# BUS_OUT.net
KiCad netlist of a schematic drawn in EAGLE
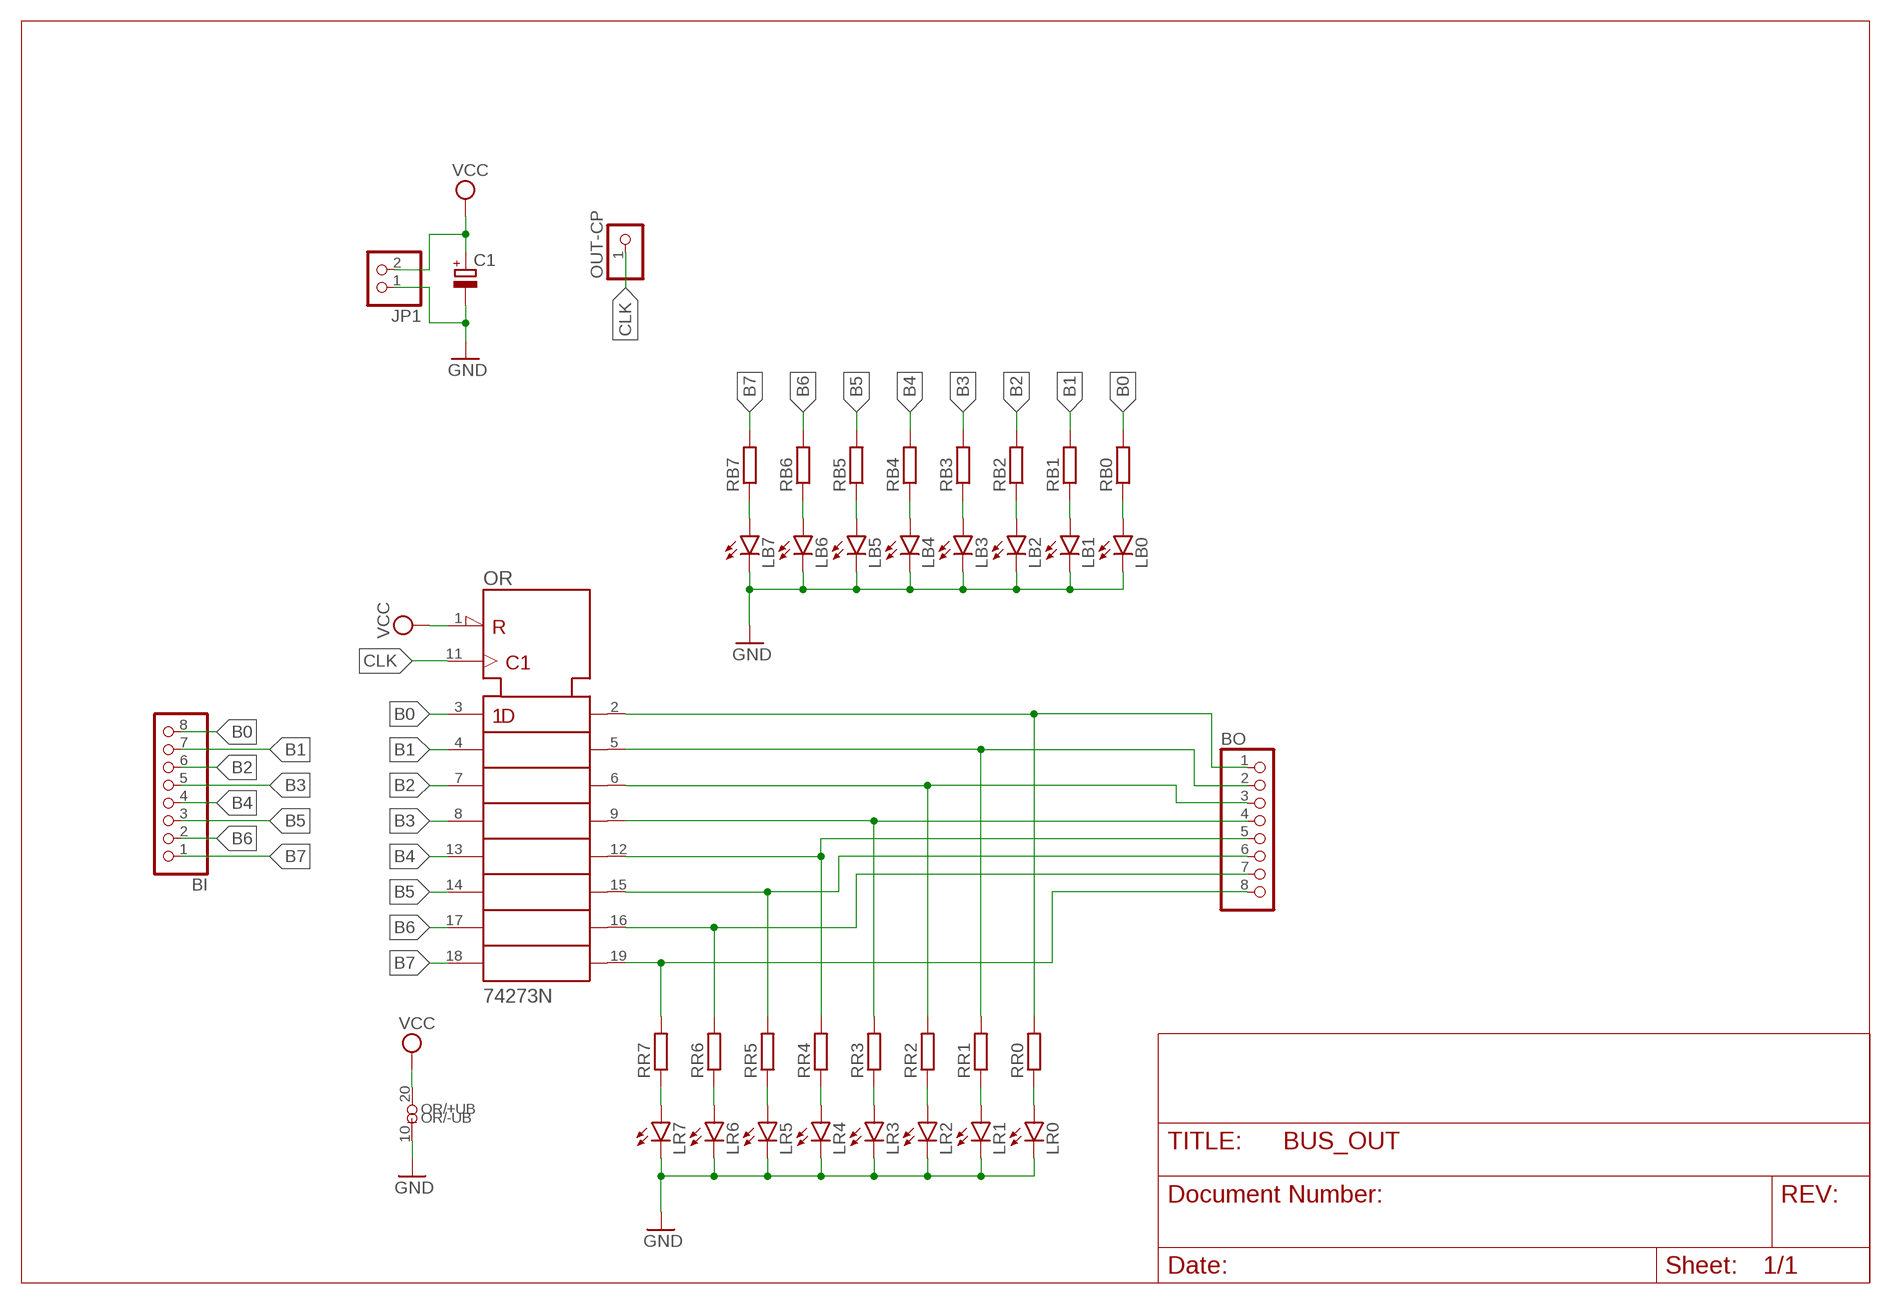
[diagram p0: schematic, sheet 1]

(export (version "E")
  (design (tool "Eeschema 10.0.6"))
  (components
    (comp (ref "BI")
      (value "PINHD-1X8")
      (footprint "eagle-import:1X08")
      (libsource (lib "eagle-import") (part "PINHD-1X8"))
    )
    (comp (ref "BO")
      (value "PINHD-1X8")
      (footprint "eagle-import:1X08")
      (libsource (lib "eagle-import") (part "PINHD-1X8"))
    )
    (comp (ref "C1")
      (value "CPOL-EUE2.5-6")
      (footprint "eagle-import:E2,5-6")
      (libsource (lib "eagle-import") (part "CPOL-EUE2.5-6"))
    )
    (comp (ref "JP1")
      (value "PINHD-1X2")
      (footprint "eagle-import:1X02")
      (libsource (lib "eagle-import") (part "PINHD-1X2"))
    )
    (comp (ref "LB0")
      (value "LED5MM")
      (footprint "eagle-import:LED5MM")
      (libsource (lib "eagle-import") (part "LED5MM"))
    )
    (comp (ref "LB1")
      (value "LED5MM")
      (footprint "eagle-import:LED5MM")
      (libsource (lib "eagle-import") (part "LED5MM"))
    )
    (comp (ref "LB2")
      (value "LED5MM")
      (footprint "eagle-import:LED5MM")
      (libsource (lib "eagle-import") (part "LED5MM"))
    )
    (comp (ref "LB3")
      (value "LED5MM")
      (footprint "eagle-import:LED5MM")
      (libsource (lib "eagle-import") (part "LED5MM"))
    )
    (comp (ref "LB4")
      (value "LED5MM")
      (footprint "eagle-import:LED5MM")
      (libsource (lib "eagle-import") (part "LED5MM"))
    )
    (comp (ref "LB5")
      (value "LED5MM")
      (footprint "eagle-import:LED5MM")
      (libsource (lib "eagle-import") (part "LED5MM"))
    )
    (comp (ref "LB6")
      (value "LED5MM")
      (footprint "eagle-import:LED5MM")
      (libsource (lib "eagle-import") (part "LED5MM"))
    )
    (comp (ref "LB7")
      (value "LED5MM")
      (footprint "eagle-import:LED5MM")
      (libsource (lib "eagle-import") (part "LED5MM"))
    )
    (comp (ref "LR0")
      (value "LED5MM")
      (footprint "eagle-import:LED5MM")
      (libsource (lib "eagle-import") (part "LED5MM"))
    )
    (comp (ref "LR1")
      (value "LED5MM")
      (footprint "eagle-import:LED5MM")
      (libsource (lib "eagle-import") (part "LED5MM"))
    )
    (comp (ref "LR2")
      (value "LED5MM")
      (footprint "eagle-import:LED5MM")
      (libsource (lib "eagle-import") (part "LED5MM"))
    )
    (comp (ref "LR3")
      (value "LED5MM")
      (footprint "eagle-import:LED5MM")
      (libsource (lib "eagle-import") (part "LED5MM"))
    )
    (comp (ref "LR4")
      (value "LED5MM")
      (footprint "eagle-import:LED5MM")
      (libsource (lib "eagle-import") (part "LED5MM"))
    )
    (comp (ref "LR5")
      (value "LED5MM")
      (footprint "eagle-import:LED5MM")
      (libsource (lib "eagle-import") (part "LED5MM"))
    )
    (comp (ref "LR6")
      (value "LED5MM")
      (footprint "eagle-import:LED5MM")
      (libsource (lib "eagle-import") (part "LED5MM"))
    )
    (comp (ref "LR7")
      (value "LED5MM")
      (footprint "eagle-import:LED5MM")
      (libsource (lib "eagle-import") (part "LED5MM"))
    )
    (comp (ref "OR")
      (value "74273N")
      (footprint "eagle-import:DIL20")
      (libsource (lib "eagle-import") (part "74273N"))
    )
    (comp (ref "OUT-CP")
      (value "PINHD-1X1")
      (footprint "eagle-import:1X01")
      (libsource (lib "eagle-import") (part "PINHD-1X1"))
    )
    (comp (ref "RB0")
      (value "R-EU_0204/7")
      (footprint "eagle-import:0204_7")
      (libsource (lib "eagle-import") (part "R-EU_0204/7"))
    )
    (comp (ref "RB1")
      (value "R-EU_0204/7")
      (footprint "eagle-import:0204_7")
      (libsource (lib "eagle-import") (part "R-EU_0204/7"))
    )
    (comp (ref "RB2")
      (value "R-EU_0204/7")
      (footprint "eagle-import:0204_7")
      (libsource (lib "eagle-import") (part "R-EU_0204/7"))
    )
    (comp (ref "RB3")
      (value "R-EU_0204/7")
      (footprint "eagle-import:0204_7")
      (libsource (lib "eagle-import") (part "R-EU_0204/7"))
    )
    (comp (ref "RB4")
      (value "R-EU_0204/7")
      (footprint "eagle-import:0204_7")
      (libsource (lib "eagle-import") (part "R-EU_0204/7"))
    )
    (comp (ref "RB5")
      (value "R-EU_0204/7")
      (footprint "eagle-import:0204_7")
      (libsource (lib "eagle-import") (part "R-EU_0204/7"))
    )
    (comp (ref "RB6")
      (value "R-EU_0204/7")
      (footprint "eagle-import:0204_7")
      (libsource (lib "eagle-import") (part "R-EU_0204/7"))
    )
    (comp (ref "RB7")
      (value "R-EU_0204/7")
      (footprint "eagle-import:0204_7")
      (libsource (lib "eagle-import") (part "R-EU_0204/7"))
    )
    (comp (ref "RR0")
      (value "R-EU_0204/7")
      (footprint "eagle-import:0204_7")
      (libsource (lib "eagle-import") (part "R-EU_0204/7"))
    )
    (comp (ref "RR1")
      (value "R-EU_0204/7")
      (footprint "eagle-import:0204_7")
      (libsource (lib "eagle-import") (part "R-EU_0204/7"))
    )
    (comp (ref "RR2")
      (value "R-EU_0204/7")
      (footprint "eagle-import:0204_7")
      (libsource (lib "eagle-import") (part "R-EU_0204/7"))
    )
    (comp (ref "RR3")
      (value "R-EU_0204/7")
      (footprint "eagle-import:0204_7")
      (libsource (lib "eagle-import") (part "R-EU_0204/7"))
    )
    (comp (ref "RR4")
      (value "R-EU_0204/7")
      (footprint "eagle-import:0204_7")
      (libsource (lib "eagle-import") (part "R-EU_0204/7"))
    )
    (comp (ref "RR5")
      (value "R-EU_0204/7")
      (footprint "eagle-import:0204_7")
      (libsource (lib "eagle-import") (part "R-EU_0204/7"))
    )
    (comp (ref "RR6")
      (value "R-EU_0204/7")
      (footprint "eagle-import:0204_7")
      (libsource (lib "eagle-import") (part "R-EU_0204/7"))
    )
    (comp (ref "RR7")
      (value "R-EU_0204/7")
      (footprint "eagle-import:0204_7")
      (libsource (lib "eagle-import") (part "R-EU_0204/7"))
    )
  )
  (nets
    (net (code "1") (name "B0") (class "Default")
      (node (ref "BI") (pin "8") (pinfunction "8_8") (pintype "passive"))
      (node (ref "OR") (pin "3") (pinfunction "1D_3") (pintype "input"))
      (node (ref "RB0") (pin "2") (pinfunction "2_2") (pintype "passive"))
    )
    (net (code "2") (name "B1") (class "Default")
      (node (ref "BI") (pin "7") (pinfunction "7_7") (pintype "passive"))
      (node (ref "OR") (pin "4") (pinfunction "2D_4") (pintype "input"))
      (node (ref "RB1") (pin "2") (pinfunction "2_2") (pintype "passive"))
    )
    (net (code "3") (name "B2") (class "Default")
      (node (ref "BI") (pin "6") (pinfunction "6_6") (pintype "passive"))
      (node (ref "OR") (pin "7") (pinfunction "3D_7") (pintype "input"))
      (node (ref "RB2") (pin "2") (pinfunction "2_2") (pintype "passive"))
    )
    (net (code "4") (name "B3") (class "Default")
      (node (ref "BI") (pin "5") (pinfunction "5_5") (pintype "passive"))
      (node (ref "OR") (pin "8") (pinfunction "4D_8") (pintype "input"))
      (node (ref "RB3") (pin "2") (pinfunction "2_2") (pintype "passive"))
    )
    (net (code "5") (name "B4") (class "Default")
      (node (ref "BI") (pin "4") (pinfunction "4_4") (pintype "passive"))
      (node (ref "OR") (pin "13") (pinfunction "5D_13") (pintype "input"))
      (node (ref "RB4") (pin "2") (pinfunction "2_2") (pintype "passive"))
    )
    (net (code "6") (name "B5") (class "Default")
      (node (ref "BI") (pin "3") (pinfunction "3_3") (pintype "passive"))
      (node (ref "OR") (pin "14") (pinfunction "6D_14") (pintype "input"))
      (node (ref "RB5") (pin "2") (pinfunction "2_2") (pintype "passive"))
    )
    (net (code "7") (name "B6") (class "Default")
      (node (ref "BI") (pin "2") (pinfunction "2_2") (pintype "passive"))
      (node (ref "OR") (pin "17") (pinfunction "7D_17") (pintype "input"))
      (node (ref "RB6") (pin "2") (pinfunction "2_2") (pintype "passive"))
    )
    (net (code "8") (name "B7") (class "Default")
      (node (ref "BI") (pin "1") (pinfunction "1_1") (pintype "passive"))
      (node (ref "OR") (pin "18") (pinfunction "8D_18") (pintype "input"))
      (node (ref "RB7") (pin "2") (pinfunction "2_2") (pintype "passive"))
    )
    (net (code "9") (name "CLK") (class "Default")
      (node (ref "OR") (pin "11") (pinfunction "CLK_11") (pintype "input"))
      (node (ref "OUT-CP") (pin "1") (pinfunction "1_1") (pintype "passive"))
    )
    (net (code "10") (name "GND") (class "Default")
      (node (ref "C1") (pin "-") (pinfunction "-_-") (pintype "passive"))
      (node (ref "JP1") (pin "1") (pinfunction "1_1") (pintype "passive"))
      (node (ref "LB0") (pin "K") (pinfunction "C_K") (pintype "passive"))
      (node (ref "LB1") (pin "K") (pinfunction "C_K") (pintype "passive"))
      (node (ref "LB2") (pin "K") (pinfunction "C_K") (pintype "passive"))
      (node (ref "LB3") (pin "K") (pinfunction "C_K") (pintype "passive"))
      (node (ref "LB4") (pin "K") (pinfunction "C_K") (pintype "passive"))
      (node (ref "LB5") (pin "K") (pinfunction "C_K") (pintype "passive"))
      (node (ref "LB6") (pin "K") (pinfunction "C_K") (pintype "passive"))
      (node (ref "LB7") (pin "K") (pinfunction "C_K") (pintype "passive"))
      (node (ref "LR0") (pin "K") (pinfunction "C_K") (pintype "passive"))
      (node (ref "LR1") (pin "K") (pinfunction "C_K") (pintype "passive"))
      (node (ref "LR2") (pin "K") (pinfunction "C_K") (pintype "passive"))
      (node (ref "LR3") (pin "K") (pinfunction "C_K") (pintype "passive"))
      (node (ref "LR4") (pin "K") (pinfunction "C_K") (pintype "passive"))
      (node (ref "LR5") (pin "K") (pinfunction "C_K") (pintype "passive"))
      (node (ref "LR6") (pin "K") (pinfunction "C_K") (pintype "passive"))
      (node (ref "LR7") (pin "K") (pinfunction "C_K") (pintype "passive"))
      (node (ref "OR") (pin "10") (pinfunction "-UB_10") (pintype "power_in"))
    )
    (net (code "11") (name "Net-(LB0-PadA)") (class "Default")
      (node (ref "LB0") (pin "A") (pinfunction "A_A") (pintype "passive"))
      (node (ref "RB0") (pin "1") (pinfunction "1_1") (pintype "passive"))
    )
    (net (code "12") (name "Net-(LB1-PadA)") (class "Default")
      (node (ref "LB1") (pin "A") (pinfunction "A_A") (pintype "passive"))
      (node (ref "RB1") (pin "1") (pinfunction "1_1") (pintype "passive"))
    )
    (net (code "13") (name "Net-(LB2-PadA)") (class "Default")
      (node (ref "LB2") (pin "A") (pinfunction "A_A") (pintype "passive"))
      (node (ref "RB2") (pin "1") (pinfunction "1_1") (pintype "passive"))
    )
    (net (code "14") (name "Net-(LB3-PadA)") (class "Default")
      (node (ref "LB3") (pin "A") (pinfunction "A_A") (pintype "passive"))
      (node (ref "RB3") (pin "1") (pinfunction "1_1") (pintype "passive"))
    )
    (net (code "15") (name "Net-(LB4-PadA)") (class "Default")
      (node (ref "LB4") (pin "A") (pinfunction "A_A") (pintype "passive"))
      (node (ref "RB4") (pin "1") (pinfunction "1_1") (pintype "passive"))
    )
    (net (code "16") (name "Net-(LB5-PadA)") (class "Default")
      (node (ref "LB5") (pin "A") (pinfunction "A_A") (pintype "passive"))
      (node (ref "RB5") (pin "1") (pinfunction "1_1") (pintype "passive"))
    )
    (net (code "17") (name "Net-(LB6-PadA)") (class "Default")
      (node (ref "LB6") (pin "A") (pinfunction "A_A") (pintype "passive"))
      (node (ref "RB6") (pin "1") (pinfunction "1_1") (pintype "passive"))
    )
    (net (code "18") (name "Net-(LB7-PadA)") (class "Default")
      (node (ref "LB7") (pin "A") (pinfunction "A_A") (pintype "passive"))
      (node (ref "RB7") (pin "1") (pinfunction "1_1") (pintype "passive"))
    )
    (net (code "19") (name "Net-(LR0-PadA)") (class "Default")
      (node (ref "LR0") (pin "A") (pinfunction "A_A") (pintype "passive"))
      (node (ref "RR0") (pin "1") (pinfunction "1_1") (pintype "passive"))
    )
    (net (code "20") (name "Net-(LR1-PadA)") (class "Default")
      (node (ref "LR1") (pin "A") (pinfunction "A_A") (pintype "passive"))
      (node (ref "RR1") (pin "1") (pinfunction "1_1") (pintype "passive"))
    )
    (net (code "21") (name "Net-(LR2-PadA)") (class "Default")
      (node (ref "LR2") (pin "A") (pinfunction "A_A") (pintype "passive"))
      (node (ref "RR2") (pin "1") (pinfunction "1_1") (pintype "passive"))
    )
    (net (code "22") (name "Net-(LR3-PadA)") (class "Default")
      (node (ref "LR3") (pin "A") (pinfunction "A_A") (pintype "passive"))
      (node (ref "RR3") (pin "1") (pinfunction "1_1") (pintype "passive"))
    )
    (net (code "23") (name "Net-(LR4-PadA)") (class "Default")
      (node (ref "LR4") (pin "A") (pinfunction "A_A") (pintype "passive"))
      (node (ref "RR4") (pin "1") (pinfunction "1_1") (pintype "passive"))
    )
    (net (code "24") (name "Net-(LR5-PadA)") (class "Default")
      (node (ref "LR5") (pin "A") (pinfunction "A_A") (pintype "passive"))
      (node (ref "RR5") (pin "1") (pinfunction "1_1") (pintype "passive"))
    )
    (net (code "25") (name "Net-(LR6-PadA)") (class "Default")
      (node (ref "LR6") (pin "A") (pinfunction "A_A") (pintype "passive"))
      (node (ref "RR6") (pin "1") (pinfunction "1_1") (pintype "passive"))
    )
    (net (code "26") (name "Net-(LR7-PadA)") (class "Default")
      (node (ref "LR7") (pin "A") (pinfunction "A_A") (pintype "passive"))
      (node (ref "RR7") (pin "1") (pinfunction "1_1") (pintype "passive"))
    )
    (net (code "27") (name "Net-(ORC-1Q)") (class "Default")
      (node (ref "BO") (pin "1") (pinfunction "1_1") (pintype "passive"))
      (node (ref "OR") (pin "2") (pinfunction "1Q_2") (pintype "output"))
      (node (ref "RR0") (pin "2") (pinfunction "2_2") (pintype "passive"))
    )
    (net (code "28") (name "Net-(ORC-2Q)") (class "Default")
      (node (ref "BO") (pin "2") (pinfunction "2_2") (pintype "passive"))
      (node (ref "OR") (pin "5") (pinfunction "2Q_5") (pintype "output"))
      (node (ref "RR1") (pin "2") (pinfunction "2_2") (pintype "passive"))
    )
    (net (code "29") (name "Net-(ORC-3Q)") (class "Default")
      (node (ref "BO") (pin "3") (pinfunction "3_3") (pintype "passive"))
      (node (ref "OR") (pin "6") (pinfunction "3Q_6") (pintype "output"))
      (node (ref "RR2") (pin "2") (pinfunction "2_2") (pintype "passive"))
    )
    (net (code "30") (name "Net-(ORC-4Q)") (class "Default")
      (node (ref "BO") (pin "4") (pinfunction "4_4") (pintype "passive"))
      (node (ref "OR") (pin "9") (pinfunction "4Q_9") (pintype "output"))
      (node (ref "RR3") (pin "2") (pinfunction "2_2") (pintype "passive"))
    )
    (net (code "31") (name "Net-(ORC-5Q)") (class "Default")
      (node (ref "BO") (pin "5") (pinfunction "5_5") (pintype "passive"))
      (node (ref "OR") (pin "12") (pinfunction "5Q_12") (pintype "output"))
      (node (ref "RR4") (pin "2") (pinfunction "2_2") (pintype "passive"))
    )
    (net (code "32") (name "Net-(ORC-6Q)") (class "Default")
      (node (ref "BO") (pin "6") (pinfunction "6_6") (pintype "passive"))
      (node (ref "OR") (pin "15") (pinfunction "6Q_15") (pintype "output"))
      (node (ref "RR5") (pin "2") (pinfunction "2_2") (pintype "passive"))
    )
    (net (code "33") (name "Net-(ORC-7Q)") (class "Default")
      (node (ref "BO") (pin "7") (pinfunction "7_7") (pintype "passive"))
      (node (ref "OR") (pin "16") (pinfunction "7Q_16") (pintype "output"))
      (node (ref "RR6") (pin "2") (pinfunction "2_2") (pintype "passive"))
    )
    (net (code "34") (name "Net-(ORC-8Q)") (class "Default")
      (node (ref "BO") (pin "8") (pinfunction "8_8") (pintype "passive"))
      (node (ref "OR") (pin "19") (pinfunction "8Q_19") (pintype "output"))
      (node (ref "RR7") (pin "2") (pinfunction "2_2") (pintype "passive"))
    )
    (net (code "35") (name "VCC") (class "Default")
      (node (ref "C1") (pin "+") (pinfunction "+_+") (pintype "passive"))
      (node (ref "JP1") (pin "2") (pinfunction "2_2") (pintype "passive"))
      (node (ref "OR") (pin "1") (pinfunction "~{CLR}_1") (pintype "input"))
      (node (ref "OR") (pin "20") (pinfunction "+UB_20") (pintype "power_in"))
    )
  )
)
